# Programmer.net
KiCad netlist of a schematic drawn in Altium Designer
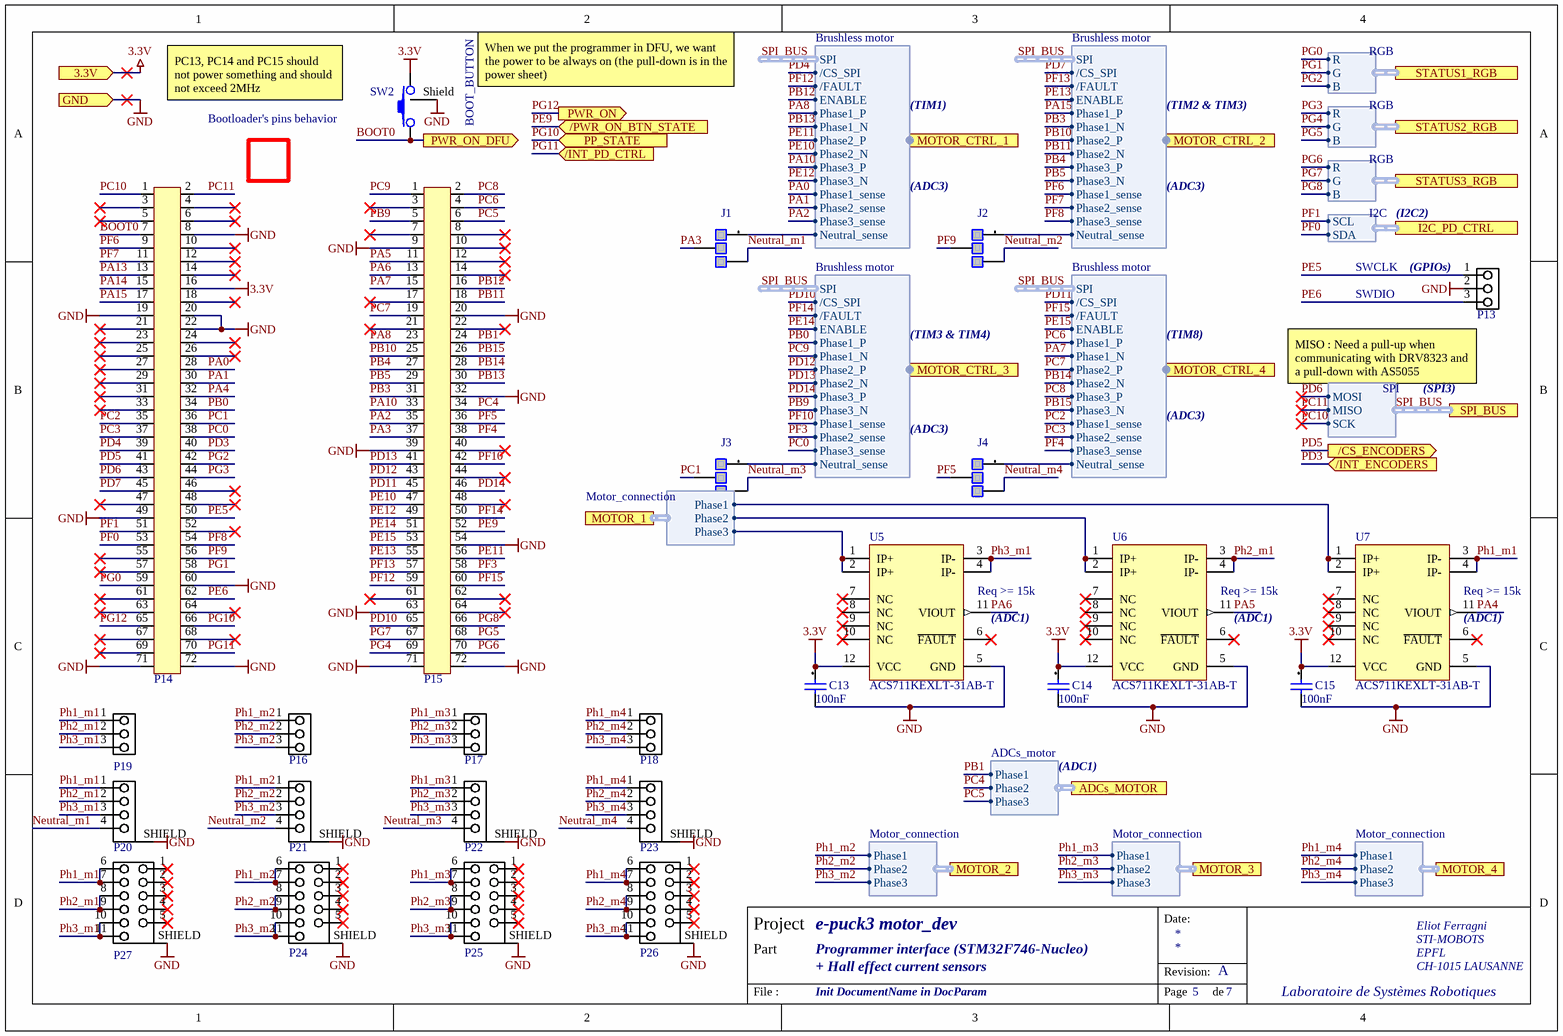
[diagram p0: Programmer.SchDoc]

(export (version "E")
  (design (tool "Eeschema 10.0.6"))
  (components
    (comp (ref "C13")
      (value "100nF")
      (footprint "CAPC1608X08L")
      (description "Capacitor TBD 0603")
      (libsource (lib "LSRO1Altium") (part "CAP-NP"))
    )
    (comp (ref "C14")
      (value "100nF")
      (footprint "CAPC1608X08L")
      (description "Capacitor TBD 0603")
      (libsource (lib "LSRO1Altium") (part "CAP-NP"))
    )
    (comp (ref "C15")
      (value "100nF")
      (footprint "CAPC1608X08L")
      (description "Capacitor TBD 0603")
      (libsource (lib "LSRO1Altium") (part "CAP-NP"))
    )
    (comp (ref "J1")
      (value "CC_SolderJP3_Micro")
      (footprint "CC_SolderJP3_U")
      (description "Micro Solder Jumper 3 leads")
      (libsource (lib "LSRO1Altium") (part "SolderJP3"))
    )
    (comp (ref "J2")
      (value "CC_SolderJP3_Micro")
      (footprint "CC_SolderJP3_U")
      (description "Micro Solder Jumper 3 leads")
      (libsource (lib "LSRO1Altium") (part "SolderJP3"))
    )
    (comp (ref "J3")
      (value "CC_SolderJP3_Micro")
      (footprint "CC_SolderJP3_U")
      (description "Micro Solder Jumper 3 leads")
      (libsource (lib "LSRO1Altium") (part "SolderJP3"))
    )
    (comp (ref "J4")
      (value "CC_SolderJP3_Micro")
      (footprint "CC_SolderJP3_U")
      (description "Micro Solder Jumper 3 leads")
      (libsource (lib "LSRO1Altium") (part "SolderJP3"))
    )
    (comp (ref "P13")
      (value "Header 3")
      (footprint "HEADER1X3-2.54")
      (description "Header, 3-Pin")
      (fields (field (name "MANUFACTURER") "Generic Components") (field (name "PUBLISHER") "Altium Limited"))
      (libsource (lib "Schlib") (part "Header 3"))
    )
    (comp (ref "P14")
      (value "Header 2x36")
      (footprint "HEADER2x36-2.54")
      (libsource (lib "Schlib") (part "Header 2x36"))
    )
    (comp (ref "P15")
      (value "Header 2x36")
      (footprint "HEADER2x36-2.54")
      (libsource (lib "Schlib") (part "Header 2x36"))
    )
    (comp (ref "P16")
      (value "3 power pads")
      (footprint "PowerPads 3 pins")
      (description "3-Pin")
      (fields (field (name "MANUFACTURER") "Generic Components") (field (name "PUBLISHER") "Altium Limited"))
      (libsource (lib "Schlib") (part "3 power pads"))
    )
    (comp (ref "P17")
      (value "3 power pads")
      (footprint "PowerPads 3 pins")
      (description "3-Pin")
      (fields (field (name "MANUFACTURER") "Generic Components") (field (name "PUBLISHER") "Altium Limited"))
      (libsource (lib "Schlib") (part "3 power pads"))
    )
    (comp (ref "P18")
      (value "3 power pads")
      (footprint "PowerPads 3 pins")
      (description "3-Pin")
      (fields (field (name "MANUFACTURER") "Generic Components") (field (name "PUBLISHER") "Altium Limited"))
      (libsource (lib "Schlib") (part "3 power pads"))
    )
    (comp (ref "P19")
      (value "3 power pads")
      (footprint "PowerPads 3 pins")
      (description "3-Pin")
      (fields (field (name "MANUFACTURER") "Generic Components") (field (name "PUBLISHER") "Altium Limited"))
      (libsource (lib "Schlib") (part "3 power pads"))
    )
    (comp (ref "P20")
      (value "MOLEX-52207-0433")
      (footprint "Molex 52207-0433")
      (libsource (lib "Schlib") (part "MOLEX-52207-0433"))
    )
    (comp (ref "P21")
      (value "MOLEX-52207-0433")
      (footprint "Molex 52207-0433")
      (libsource (lib "Schlib") (part "MOLEX-52207-0433"))
    )
    (comp (ref "P22")
      (value "MOLEX-52207-0433")
      (footprint "Molex 52207-0433")
      (libsource (lib "Schlib") (part "MOLEX-52207-0433"))
    )
    (comp (ref "P23")
      (value "MOLEX-52207-0433")
      (footprint "Molex 52207-0433")
      (libsource (lib "Schlib") (part "MOLEX-52207-0433"))
    )
    (comp (ref "P24")
      (value "MOLEX-52207-1133")
      (footprint "Molex 52207-1133")
      (libsource (lib "Schlib") (part "MOLEX-52207-1133"))
    )
    (comp (ref "P25")
      (value "MOLEX-52207-1133")
      (footprint "Molex 52207-1133")
      (libsource (lib "Schlib") (part "MOLEX-52207-1133"))
    )
    (comp (ref "P26")
      (value "MOLEX-52207-1133")
      (footprint "Molex 52207-1133")
      (libsource (lib "Schlib") (part "MOLEX-52207-1133"))
    )
    (comp (ref "P27")
      (value "MOLEX-52207-1133")
      (footprint "Molex 52207-1133")
      (libsource (lib "Schlib") (part "MOLEX-52207-1133"))
    )
    (comp (ref "SW2")
      (value "button")
      (footprint "C&K_KMR2")
      (description "KMR221GLFS")
      (fields (field (name "MANUFACTURER") "Tyco"))
      (libsource (lib "Schlib") (part "C&K KMR2"))
    )
    (comp (ref "U5")
      (value "ACS711KEXLT-31AB-T")
      (footprint "12-PowerWFQFN")
      (libsource (lib "Schlib") (part "ACS711KEXLT-31AB-T"))
    )
    (comp (ref "U6")
      (value "ACS711KEXLT-31AB-T")
      (footprint "12-PowerWFQFN")
      (libsource (lib "Schlib") (part "ACS711KEXLT-31AB-T"))
    )
    (comp (ref "U7")
      (value "ACS711KEXLT-31AB-T")
      (footprint "12-PowerWFQFN")
      (libsource (lib "Schlib") (part "ACS711KEXLT-31AB-T"))
    )
  )
  (nets
    (net (code "16") (name "/BOOT0") (class "Default")
      (node (ref "P14") (pin "7") (pinfunction "7_7") (pintype "passive"))
      (node (ref "SW2") (pin "1") (pintype "passive"))
    )
    (net (code "21") (name "/Neutral_m1") (class "Default")
      (node (ref "J1") (pin "3") (pintype "passive"))
      (node (ref "P20") (pin "4") (pinfunction "4_4") (pintype "passive"))
    )
    (net (code "22") (name "/Neutral_m2") (class "Default")
      (node (ref "J2") (pin "3") (pintype "passive"))
      (node (ref "P21") (pin "4") (pinfunction "4_4") (pintype "passive"))
    )
    (net (code "23") (name "/Neutral_m3") (class "Default")
      (node (ref "J3") (pin "3") (pintype "passive"))
      (node (ref "P22") (pin "4") (pinfunction "4_4") (pintype "passive"))
    )
    (net (code "24") (name "/Neutral_m4") (class "Default")
      (node (ref "J4") (pin "3") (pintype "passive"))
      (node (ref "P23") (pin "4") (pinfunction "4_4") (pintype "passive"))
    )
    (net (code "25") (name "/PA0") (class "Default")
      (node (ref "P14") (pin "28") (pinfunction "28_28") (pintype "passive"))
    )
    (net (code "26") (name "/PA1") (class "Default")
      (node (ref "P14") (pin "30") (pinfunction "30_30") (pintype "passive"))
    )
    (net (code "27") (name "/PA2") (class "Default")
      (node (ref "P15") (pin "35") (pinfunction "35_35") (pintype "passive"))
    )
    (net (code "28") (name "/PA3") (class "Default")
      (node (ref "J1") (pin "2") (pintype "passive"))
      (node (ref "P15") (pin "37") (pinfunction "37_37") (pintype "passive"))
    )
    (net (code "29") (name "/PA4") (class "Default")
      (node (ref "P14") (pin "32") (pinfunction "32_32") (pintype "passive"))
      (node (ref "U7") (pin "11") (pinfunction "VIOUT_11") (pintype "output"))
    )
    (net (code "30") (name "/PA5") (class "Default")
      (node (ref "P15") (pin "11") (pinfunction "11_11") (pintype "passive"))
      (node (ref "U6") (pin "11") (pinfunction "VIOUT_11") (pintype "output"))
    )
    (net (code "31") (name "/PA6") (class "Default")
      (node (ref "P15") (pin "13") (pinfunction "13_13") (pintype "passive"))
      (node (ref "U5") (pin "11") (pinfunction "VIOUT_11") (pintype "output"))
    )
    (net (code "32") (name "/PA7") (class "Default")
      (node (ref "P15") (pin "15") (pinfunction "15_15") (pintype "passive"))
    )
    (net (code "33") (name "/PA8") (class "Default")
      (node (ref "P15") (pin "23") (pinfunction "23_23") (pintype "passive"))
    )
    (net (code "34") (name "/PA10") (class "Default")
      (node (ref "P15") (pin "33") (pinfunction "33_33") (pintype "passive"))
    )
    (net (code "35") (name "/PA13") (class "Default")
      (node (ref "P14") (pin "13") (pinfunction "13_13") (pintype "passive"))
    )
    (net (code "36") (name "/PA14") (class "Default")
      (node (ref "P14") (pin "15") (pinfunction "15_15") (pintype "passive"))
    )
    (net (code "37") (name "/PA15") (class "Default")
      (node (ref "P14") (pin "17") (pinfunction "17_17") (pintype "passive"))
    )
    (net (code "38") (name "/PB0") (class "Default")
      (node (ref "P14") (pin "34") (pinfunction "34_34") (pintype "passive"))
    )
    (net (code "39") (name "/PB1") (class "Default")
      (node (ref "P15") (pin "24") (pinfunction "24_24") (pintype "passive"))
    )
    (net (code "40") (name "/PB3") (class "Default")
      (node (ref "P15") (pin "31") (pinfunction "31_31") (pintype "passive"))
    )
    (net (code "41") (name "/PB4") (class "Default")
      (node (ref "P15") (pin "27") (pinfunction "27_27") (pintype "passive"))
    )
    (net (code "42") (name "/PB5") (class "Default")
      (node (ref "P15") (pin "29") (pinfunction "29_29") (pintype "passive"))
    )
    (net (code "43") (name "/PB9") (class "Default")
      (node (ref "P15") (pin "5") (pinfunction "5_5") (pintype "passive"))
    )
    (net (code "44") (name "/PB10") (class "Default")
      (node (ref "P15") (pin "25") (pinfunction "25_25") (pintype "passive"))
    )
    (net (code "45") (name "/PB11") (class "Default")
      (node (ref "P15") (pin "18") (pinfunction "18_18") (pintype "passive"))
    )
    (net (code "46") (name "/PB12") (class "Default")
      (node (ref "P15") (pin "16") (pinfunction "16_16") (pintype "passive"))
    )
    (net (code "47") (name "/PB13") (class "Default")
      (node (ref "P15") (pin "30") (pinfunction "30_30") (pintype "passive"))
    )
    (net (code "48") (name "/PB14") (class "Default")
      (node (ref "P15") (pin "28") (pinfunction "28_28") (pintype "passive"))
    )
    (net (code "49") (name "/PB15") (class "Default")
      (node (ref "P15") (pin "26") (pinfunction "26_26") (pintype "passive"))
    )
    (net (code "50") (name "/PC0") (class "Default")
      (node (ref "P14") (pin "38") (pinfunction "38_38") (pintype "passive"))
    )
    (net (code "51") (name "/PC1") (class "Default")
      (node (ref "J3") (pin "2") (pintype "passive"))
      (node (ref "P14") (pin "36") (pinfunction "36_36") (pintype "passive"))
    )
    (net (code "52") (name "/PC2") (class "Default")
      (node (ref "P14") (pin "35") (pinfunction "35_35") (pintype "passive"))
    )
    (net (code "53") (name "/PC3") (class "Default")
      (node (ref "P14") (pin "37") (pinfunction "37_37") (pintype "passive"))
    )
    (net (code "54") (name "/PC4") (class "Default")
      (node (ref "P15") (pin "34") (pinfunction "34_34") (pintype "passive"))
    )
    (net (code "55") (name "/PC5") (class "Default")
      (node (ref "P15") (pin "6") (pinfunction "6_6") (pintype "passive"))
    )
    (net (code "56") (name "/PC6") (class "Default")
      (node (ref "P15") (pin "4") (pinfunction "4_4") (pintype "passive"))
    )
    (net (code "57") (name "/PC7") (class "Default")
      (node (ref "P15") (pin "19") (pinfunction "19_19") (pintype "passive"))
    )
    (net (code "58") (name "/PC8") (class "Default")
      (node (ref "P15") (pin "2") (pinfunction "2_2") (pintype "passive"))
    )
    (net (code "59") (name "/PC9") (class "Default")
      (node (ref "P15") (pin "1") (pinfunction "1_1") (pintype "passive"))
    )
    (net (code "60") (name "/PC10") (class "Default")
      (node (ref "P14") (pin "1") (pinfunction "1_1") (pintype "passive+no_connect"))
    )
    (net (code "61") (name "/PC11") (class "Default")
      (node (ref "P14") (pin "2") (pinfunction "2_2") (pintype "passive+no_connect"))
    )
    (net (code "62") (name "/PD3") (class "Default")
      (node (ref "P14") (pin "40") (pinfunction "40_40") (pintype "passive"))
    )
    (net (code "63") (name "/PD4") (class "Default")
      (node (ref "P14") (pin "39") (pinfunction "39_39") (pintype "passive"))
    )
    (net (code "64") (name "/PD5") (class "Default")
      (node (ref "P14") (pin "41") (pinfunction "41_41") (pintype "passive"))
    )
    (net (code "65") (name "/PD6") (class "Default")
      (node (ref "P14") (pin "43") (pinfunction "43_43") (pintype "passive+no_connect"))
    )
    (net (code "66") (name "/PD7") (class "Default")
      (node (ref "P14") (pin "45") (pinfunction "45_45") (pintype "passive"))
    )
    (net (code "67") (name "/PD10") (class "Default")
      (node (ref "P15") (pin "65") (pinfunction "57_65") (pintype "passive"))
    )
    (net (code "68") (name "/PD11") (class "Default")
      (node (ref "P15") (pin "45") (pinfunction "45_45") (pintype "passive"))
    )
    (net (code "69") (name "/PD12") (class "Default")
      (node (ref "P15") (pin "43") (pinfunction "43_43") (pintype "passive"))
    )
    (net (code "70") (name "/PD13") (class "Default")
      (node (ref "P15") (pin "41") (pinfunction "41_41") (pintype "passive"))
    )
    (net (code "71") (name "/PD14") (class "Default")
      (node (ref "P15") (pin "46") (pinfunction "46_46") (pintype "passive"))
    )
    (net (code "72") (name "/PE5") (class "Default")
      (node (ref "P13") (pin "1") (pinfunction "1_1") (pintype "passive"))
      (node (ref "P14") (pin "50") (pinfunction "50_50") (pintype "passive"))
    )
    (net (code "73") (name "/PE6") (class "Default")
      (node (ref "P13") (pin "3") (pinfunction "3_3") (pintype "passive"))
      (node (ref "P14") (pin "62") (pinfunction "56_62") (pintype "passive"))
    )
    (net (code "74") (name "/PE9") (class "Default")
      (node (ref "P15") (pin "52") (pinfunction "51_52") (pintype "passive"))
    )
    (net (code "75") (name "/PE10") (class "Default")
      (node (ref "P15") (pin "47") (pinfunction "47_47") (pintype "passive"))
    )
    (net (code "76") (name "/PE11") (class "Default")
      (node (ref "P15") (pin "56") (pinfunction "53_56") (pintype "passive"))
    )
    (net (code "77") (name "/PE12") (class "Default")
      (node (ref "P15") (pin "49") (pinfunction "49_49") (pintype "passive"))
    )
    (net (code "78") (name "/PE13") (class "Default")
      (node (ref "P15") (pin "55") (pinfunction "52_55") (pintype "passive"))
    )
    (net (code "79") (name "/PE14") (class "Default")
      (node (ref "P15") (pin "51") (pinfunction "50_51") (pintype "passive"))
    )
    (net (code "80") (name "/PE15") (class "Default")
      (node (ref "P15") (pin "53") (pinfunction "51_53") (pintype "passive"))
    )
    (net (code "81") (name "/PF0") (class "Default")
      (node (ref "P14") (pin "53") (pinfunction "51_53") (pintype "passive"))
    )
    (net (code "82") (name "/PF1") (class "Default")
      (node (ref "P14") (pin "51") (pinfunction "50_51") (pintype "passive"))
    )
    (net (code "83") (name "/PF3") (class "Default")
      (node (ref "P15") (pin "58") (pinfunction "54_58") (pintype "passive"))
    )
    (net (code "84") (name "/PF4") (class "Default")
      (node (ref "P15") (pin "38") (pinfunction "38_38") (pintype "passive"))
    )
    (net (code "85") (name "/PF5") (class "Default")
      (node (ref "J4") (pin "2") (pintype "passive"))
      (node (ref "P15") (pin "36") (pinfunction "36_36") (pintype "passive"))
    )
    (net (code "86") (name "/PF6") (class "Default")
      (node (ref "P14") (pin "9") (pinfunction "9_9") (pintype "passive"))
    )
    (net (code "87") (name "/PF7") (class "Default")
      (node (ref "P14") (pin "11") (pinfunction "11_11") (pintype "passive"))
    )
    (net (code "88") (name "/PF8") (class "Default")
      (node (ref "P14") (pin "54") (pinfunction "52_54") (pintype "passive"))
    )
    (net (code "89") (name "/PF9") (class "Default")
      (node (ref "J2") (pin "2") (pintype "passive"))
      (node (ref "P14") (pin "56") (pinfunction "53_56") (pintype "passive"))
    )
    (net (code "90") (name "/PF10") (class "Default")
      (node (ref "P15") (pin "42") (pinfunction "42_42") (pintype "passive"))
    )
    (net (code "91") (name "/PF12") (class "Default")
      (node (ref "P15") (pin "59") (pinfunction "54_59") (pintype "passive"))
    )
    (net (code "92") (name "/PF13") (class "Default")
      (node (ref "P15") (pin "57") (pinfunction "53_57") (pintype "passive"))
    )
    (net (code "93") (name "/PF14") (class "Default")
      (node (ref "P15") (pin "50") (pinfunction "50_50") (pintype "passive"))
    )
    (net (code "94") (name "/PF15") (class "Default")
      (node (ref "P15") (pin "60") (pinfunction "55_60") (pintype "passive"))
    )
    (net (code "95") (name "/PG0") (class "Default")
      (node (ref "P14") (pin "59") (pinfunction "54_59") (pintype "passive"))
    )
    (net (code "96") (name "/PG1") (class "Default")
      (node (ref "P14") (pin "58") (pinfunction "54_58") (pintype "passive"))
    )
    (net (code "97") (name "/PG2") (class "Default")
      (node (ref "P14") (pin "42") (pinfunction "42_42") (pintype "passive"))
    )
    (net (code "98") (name "/PG3") (class "Default")
      (node (ref "P14") (pin "44") (pinfunction "44_44") (pintype "passive"))
    )
    (net (code "99") (name "/PG4") (class "Default")
      (node (ref "P15") (pin "69") (pinfunction "59_69") (pintype "passive"))
    )
    (net (code "100") (name "/PG5") (class "Default")
      (node (ref "P15") (pin "68") (pinfunction "59_68") (pintype "passive"))
    )
    (net (code "101") (name "/PG6") (class "Default")
      (node (ref "P15") (pin "70") (pinfunction "60_70") (pintype "passive"))
    )
    (net (code "102") (name "/PG7") (class "Default")
      (node (ref "P15") (pin "67") (pinfunction "58_67") (pintype "passive"))
    )
    (net (code "103") (name "/PG8") (class "Default")
      (node (ref "P15") (pin "66") (pinfunction "58_66") (pintype "passive"))
    )
    (net (code "104") (name "/PG10") (class "Default")
      (node (ref "P14") (pin "66") (pinfunction "58_66") (pintype "passive"))
    )
    (net (code "105") (name "/PG11") (class "Default")
      (node (ref "P14") (pin "70") (pinfunction "60_70") (pintype "passive"))
    )
    (net (code "106") (name "/PG12") (class "Default")
      (node (ref "P14") (pin "65") (pinfunction "57_65") (pintype "passive"))
    )
    (net (code "107") (name "/Ph1_m1") (class "Default")
      (node (ref "P19") (pin "1") (pinfunction "1_1") (pintype "passive"))
      (node (ref "P20") (pin "1") (pinfunction "1_1") (pintype "passive"))
      (node (ref "P27") (pin "6") (pinfunction "6_6") (pintype "passive"))
      (node (ref "P27") (pin "7") (pinfunction "7_7") (pintype "passive"))
      (node (ref "U7") (pin "3") (pinfunction "IP-_3") (pintype "power_in"))
      (node (ref "U7") (pin "4") (pinfunction "IP-_4") (pintype "power_in"))
    )
    (net (code "108") (name "/Ph1_m2") (class "Default")
      (node (ref "P16") (pin "1") (pinfunction "1_1") (pintype "passive"))
      (node (ref "P21") (pin "1") (pinfunction "1_1") (pintype "passive"))
      (node (ref "P24") (pin "6") (pinfunction "6_6") (pintype "passive"))
      (node (ref "P24") (pin "7") (pinfunction "7_7") (pintype "passive"))
    )
    (net (code "109") (name "/Ph1_m3") (class "Default")
      (node (ref "P17") (pin "1") (pinfunction "1_1") (pintype "passive"))
      (node (ref "P22") (pin "1") (pinfunction "1_1") (pintype "passive"))
      (node (ref "P25") (pin "6") (pinfunction "6_6") (pintype "passive"))
      (node (ref "P25") (pin "7") (pinfunction "7_7") (pintype "passive"))
    )
    (net (code "110") (name "/Ph1_m4") (class "Default")
      (node (ref "P18") (pin "1") (pinfunction "1_1") (pintype "passive"))
      (node (ref "P23") (pin "1") (pinfunction "1_1") (pintype "passive"))
      (node (ref "P26") (pin "6") (pinfunction "6_6") (pintype "passive"))
      (node (ref "P26") (pin "7") (pinfunction "7_7") (pintype "passive"))
    )
    (net (code "111") (name "/Ph2_m1") (class "Default")
      (node (ref "P19") (pin "2") (pinfunction "2_2") (pintype "passive"))
      (node (ref "P20") (pin "2") (pinfunction "2_2") (pintype "passive"))
      (node (ref "P27") (pin "8") (pinfunction "8_8") (pintype "passive"))
      (node (ref "P27") (pin "9") (pinfunction "9_9") (pintype "passive"))
      (node (ref "U6") (pin "3") (pinfunction "IP-_3") (pintype "power_in"))
      (node (ref "U6") (pin "4") (pinfunction "IP-_4") (pintype "power_in"))
    )
    (net (code "112") (name "/Ph2_m2") (class "Default")
      (node (ref "P16") (pin "2") (pinfunction "2_2") (pintype "passive"))
      (node (ref "P21") (pin "2") (pinfunction "2_2") (pintype "passive"))
      (node (ref "P24") (pin "8") (pinfunction "8_8") (pintype "passive"))
      (node (ref "P24") (pin "9") (pinfunction "9_9") (pintype "passive"))
    )
    (net (code "113") (name "/Ph2_m3") (class "Default")
      (node (ref "P17") (pin "2") (pinfunction "2_2") (pintype "passive"))
      (node (ref "P22") (pin "2") (pinfunction "2_2") (pintype "passive"))
      (node (ref "P25") (pin "8") (pinfunction "8_8") (pintype "passive"))
      (node (ref "P25") (pin "9") (pinfunction "9_9") (pintype "passive"))
    )
    (net (code "114") (name "/Ph2_m4") (class "Default")
      (node (ref "P18") (pin "2") (pinfunction "2_2") (pintype "passive"))
      (node (ref "P23") (pin "2") (pinfunction "2_2") (pintype "passive"))
      (node (ref "P26") (pin "8") (pinfunction "8_8") (pintype "passive"))
      (node (ref "P26") (pin "9") (pinfunction "9_9") (pintype "passive"))
    )
    (net (code "115") (name "/Ph3_m1") (class "Default")
      (node (ref "P19") (pin "3") (pinfunction "3_3") (pintype "passive"))
      (node (ref "P20") (pin "3") (pinfunction "3_3") (pintype "passive"))
      (node (ref "P27") (pin "10") (pinfunction "10_10") (pintype "passive"))
      (node (ref "P27") (pin "11") (pinfunction "11_11") (pintype "passive"))
      (node (ref "U5") (pin "3") (pinfunction "IP-_3") (pintype "power_in"))
      (node (ref "U5") (pin "4") (pinfunction "IP-_4") (pintype "power_in"))
    )
    (net (code "116") (name "/Ph3_m2") (class "Default")
      (node (ref "P16") (pin "3") (pinfunction "3_3") (pintype "passive"))
      (node (ref "P21") (pin "3") (pinfunction "3_3") (pintype "passive"))
      (node (ref "P24") (pin "10") (pinfunction "10_10") (pintype "passive"))
      (node (ref "P24") (pin "11") (pinfunction "11_11") (pintype "passive"))
    )
    (net (code "117") (name "/Ph3_m3") (class "Default")
      (node (ref "P17") (pin "3") (pinfunction "3_3") (pintype "passive"))
      (node (ref "P22") (pin "3") (pinfunction "3_3") (pintype "passive"))
      (node (ref "P25") (pin "10") (pinfunction "10_10") (pintype "passive"))
      (node (ref "P25") (pin "11") (pinfunction "11_11") (pintype "passive"))
    )
    (net (code "118") (name "/Ph3_m4") (class "Default")
      (node (ref "P18") (pin "3") (pinfunction "3_3") (pintype "passive"))
      (node (ref "P23") (pin "3") (pinfunction "3_3") (pintype "passive"))
      (node (ref "P26") (pin "10") (pinfunction "10_10") (pintype "passive"))
      (node (ref "P26") (pin "11") (pinfunction "11_11") (pintype "passive"))
    )
    (net (code "125") (name "3.3V") (class "Default")
      (node (ref "C13") (pin "1") (pinfunction "1_1") (pintype "passive"))
      (node (ref "C14") (pin "1") (pinfunction "1_1") (pintype "passive"))
      (node (ref "C15") (pin "1") (pinfunction "1_1") (pintype "passive"))
      (node (ref "P14") (pin "16") (pinfunction "16_16") (pintype "passive"))
      (node (ref "SW2") (pin "2") (pintype "passive"))
      (node (ref "U5") (pin "12") (pinfunction "VCC_12") (pintype "power_in"))
      (node (ref "U6") (pin "12") (pinfunction "VCC_12") (pintype "power_in"))
      (node (ref "U7") (pin "12") (pinfunction "VCC_12") (pintype "power_in"))
    )
    (net (code "126") (name "GND") (class "Default")
      (node (ref "C13") (pin "2") (pinfunction "2_2") (pintype "passive"))
      (node (ref "C14") (pin "2") (pinfunction "2_2") (pintype "passive"))
      (node (ref "C15") (pin "2") (pinfunction "2_2") (pintype "passive"))
      (node (ref "P13") (pin "2") (pinfunction "2_2") (pintype "passive"))
      (node (ref "P14") (pin "19") (pinfunction "19_19") (pintype "passive"))
      (node (ref "P14") (pin "20") (pinfunction "20_20") (pintype "passive"))
      (node (ref "P14") (pin "22") (pinfunction "22_22") (pintype "passive"))
      (node (ref "P14") (pin "49") (pinfunction "49_49") (pintype "passive"))
      (node (ref "P14") (pin "60") (pinfunction "55_60") (pintype "passive"))
      (node (ref "P14") (pin "71") (pinfunction "60_71") (pintype "passive"))
      (node (ref "P14") (pin "72") (pinfunction "61_72") (pintype "passive"))
      (node (ref "P14") (pin "8") (pinfunction "8_8") (pintype "passive"))
      (node (ref "P15") (pin "20") (pinfunction "20_20") (pintype "passive"))
      (node (ref "P15") (pin "32") (pinfunction "32_32") (pintype "passive"))
      (node (ref "P15") (pin "39") (pinfunction "39_39") (pintype "passive"))
      (node (ref "P15") (pin "54") (pinfunction "52_54") (pintype "passive"))
      (node (ref "P15") (pin "63") (pinfunction "56_63") (pintype "passive"))
      (node (ref "P15") (pin "71") (pinfunction "60_71") (pintype "passive"))
      (node (ref "P15") (pin "72") (pinfunction "61_72") (pintype "passive"))
      (node (ref "P15") (pin "9") (pinfunction "9_9") (pintype "passive"))
      (node (ref "P20") (pin "SHIELD") (pinfunction "SHIELD_SHIELD") (pintype "passive"))
      (node (ref "P21") (pin "SHIELD") (pinfunction "SHIELD_SHIELD") (pintype "passive"))
      (node (ref "P22") (pin "SHIELD") (pinfunction "SHIELD_SHIELD") (pintype "passive"))
      (node (ref "P23") (pin "SHIELD") (pinfunction "SHIELD_SHIELD") (pintype "passive"))
      (node (ref "P24") (pin "SHIELD") (pinfunction "SHIELD_SHIELD") (pintype "passive"))
      (node (ref "P25") (pin "SHIELD") (pinfunction "SHIELD_SHIELD") (pintype "passive"))
      (node (ref "P26") (pin "SHIELD") (pinfunction "SHIELD_SHIELD") (pintype "passive"))
      (node (ref "P27") (pin "SHIELD") (pinfunction "SHIELD_SHIELD") (pintype "passive"))
      (node (ref "SW2") (pin "Shield") (pinfunction "Shield_Shield") (pintype "passive"))
      (node (ref "U5") (pin "5") (pinfunction "GND_5") (pintype "power_in"))
      (node (ref "U6") (pin "5") (pinfunction "GND_5") (pintype "power_in"))
      (node (ref "U7") (pin "5") (pinfunction "GND_5") (pintype "power_in"))
    )
    (net (code "127") (name "Net-(U5-IP+-Pad1)") (class "Default")
      (node (ref "U5") (pin "1") (pinfunction "IP+_1") (pintype "power_in"))
      (node (ref "U5") (pin "2") (pinfunction "IP+_2") (pintype "power_in"))
    )
    (net (code "128") (name "Net-(U6-IP+-Pad1)") (class "Default")
      (node (ref "U6") (pin "1") (pinfunction "IP+_1") (pintype "power_in"))
      (node (ref "U6") (pin "2") (pinfunction "IP+_2") (pintype "power_in"))
    )
    (net (code "129") (name "Net-(U7-IP+-Pad1)") (class "Default")
      (node (ref "U7") (pin "1") (pinfunction "IP+_1") (pintype "power_in"))
      (node (ref "U7") (pin "2") (pinfunction "IP+_2") (pintype "power_in"))
    )
    (net (code "130") (name "unconnected-(J1-Pad1)") (class "Default")
      (node (ref "J1") (pin "1") (pintype "passive"))
    )
    (net (code "131") (name "unconnected-(J2-Pad1)") (class "Default")
      (node (ref "J2") (pin "1") (pintype "passive"))
    )
    (net (code "132") (name "unconnected-(J3-Pad1)") (class "Default")
      (node (ref "J3") (pin "1") (pintype "passive"))
    )
    (net (code "133") (name "unconnected-(J4-Pad1)") (class "Default")
      (node (ref "J4") (pin "1") (pintype "passive"))
    )
    (net (code "134") (name "unconnected-(P14-51-Pad52)") (class "Default")
      (node (ref "P14") (pin "52") (pinfunction "51_52") (pintype "passive+no_connect"))
    )
    (net (code "135") (name "unconnected-(P14-52-Pad55)") (class "Default")
      (node (ref "P14") (pin "55") (pinfunction "52_55") (pintype "passive+no_connect"))
    )
    (net (code "136") (name "unconnected-(P14-53-Pad57)") (class "Default")
      (node (ref "P14") (pin "57") (pinfunction "53_57") (pintype "passive+no_connect"))
    )
    (net (code "137") (name "unconnected-(P14-55-Pad61)") (class "Default")
      (node (ref "P14") (pin "61") (pinfunction "55_61") (pintype "passive+no_connect"))
    )
    (net (code "138") (name "unconnected-(P14-56-Pad63)") (class "Default")
      (node (ref "P14") (pin "63") (pinfunction "56_63") (pintype "passive+no_connect"))
    )
    (net (code "139") (name "unconnected-(P14-57-Pad64)") (class "Default")
      (node (ref "P14") (pin "64") (pinfunction "57_64") (pintype "passive+no_connect"))
    )
    (net (code "140") (name "unconnected-(P14-58-Pad67)") (class "Default")
      (node (ref "P14") (pin "67") (pinfunction "58_67") (pintype "passive+no_connect"))
    )
    (net (code "141") (name "unconnected-(P14-59-Pad68)") (class "Default")
      (node (ref "P14") (pin "68") (pinfunction "59_68") (pintype "passive+no_connect"))
    )
    (net (code "142") (name "unconnected-(P14-59-Pad69)") (class "Default")
      (node (ref "P14") (pin "69") (pinfunction "59_69") (pintype "passive+no_connect"))
    )
    (net (code "143") (name "unconnected-(P14-Pad3)") (class "Default")
      (node (ref "P14") (pin "3") (pinfunction "3_3") (pintype "passive+no_connect"))
    )
    (net (code "144") (name "unconnected-(P14-Pad4)") (class "Default")
      (node (ref "P14") (pin "4") (pinfunction "4_4") (pintype "passive+no_connect"))
    )
    (net (code "145") (name "unconnected-(P14-Pad5)") (class "Default")
      (node (ref "P14") (pin "5") (pinfunction "5_5") (pintype "passive+no_connect"))
    )
    (net (code "146") (name "unconnected-(P14-Pad6)") (class "Default")
      (node (ref "P14") (pin "6") (pinfunction "6_6") (pintype "passive+no_connect"))
    )
    (net (code "147") (name "unconnected-(P14-Pad10)") (class "Default")
      (node (ref "P14") (pin "10") (pinfunction "10_10") (pintype "passive+no_connect"))
    )
    (net (code "148") (name "unconnected-(P14-Pad12)") (class "Default")
      (node (ref "P14") (pin "12") (pinfunction "12_12") (pintype "passive+no_connect"))
    )
    (net (code "149") (name "unconnected-(P14-Pad14)") (class "Default")
      (node (ref "P14") (pin "14") (pinfunction "14_14") (pintype "passive+no_connect"))
    )
    (net (code "150") (name "unconnected-(P14-Pad18)") (class "Default")
      (node (ref "P14") (pin "18") (pinfunction "18_18") (pintype "passive+no_connect"))
    )
    (net (code "151") (name "unconnected-(P14-Pad21)") (class "Default")
      (node (ref "P14") (pin "21") (pinfunction "21_21") (pintype "passive+no_connect"))
    )
    (net (code "152") (name "unconnected-(P14-Pad23)") (class "Default")
      (node (ref "P14") (pin "23") (pinfunction "23_23") (pintype "passive+no_connect"))
    )
    (net (code "153") (name "unconnected-(P14-Pad24)") (class "Default")
      (node (ref "P14") (pin "24") (pinfunction "24_24") (pintype "passive+no_connect"))
    )
    (net (code "154") (name "unconnected-(P14-Pad25)") (class "Default")
      (node (ref "P14") (pin "25") (pinfunction "25_25") (pintype "passive+no_connect"))
    )
    (net (code "155") (name "unconnected-(P14-Pad26)") (class "Default")
      (node (ref "P14") (pin "26") (pinfunction "26_26") (pintype "passive+no_connect"))
    )
    (net (code "156") (name "unconnected-(P14-Pad27)") (class "Default")
      (node (ref "P14") (pin "27") (pinfunction "27_27") (pintype "passive+no_connect"))
    )
    (net (code "157") (name "unconnected-(P14-Pad29)") (class "Default")
      (node (ref "P14") (pin "29") (pinfunction "29_29") (pintype "passive+no_connect"))
    )
    (net (code "158") (name "unconnected-(P14-Pad31)") (class "Default")
      (node (ref "P14") (pin "31") (pinfunction "31_31") (pintype "passive+no_connect"))
    )
    (net (code "159") (name "unconnected-(P14-Pad33)") (class "Default")
      (node (ref "P14") (pin "33") (pinfunction "33_33") (pintype "passive+no_connect"))
    )
    (net (code "160") (name "unconnected-(P14-Pad46)") (class "Default")
      (node (ref "P14") (pin "46") (pinfunction "46_46") (pintype "passive+no_connect"))
    )
    (net (code "161") (name "unconnected-(P14-Pad47)") (class "Default")
      (node (ref "P14") (pin "47") (pinfunction "47_47") (pintype "passive+no_connect"))
    )
    (net (code "162") (name "unconnected-(P14-Pad48)") (class "Default")
      (node (ref "P14") (pin "48") (pinfunction "48_48") (pintype "passive+no_connect"))
    )
    (net (code "163") (name "unconnected-(P15-55-Pad61)") (class "Default")
      (node (ref "P15") (pin "61") (pinfunction "55_61") (pintype "passive+no_connect"))
    )
    (net (code "164") (name "unconnected-(P15-56-Pad62)") (class "Default")
      (node (ref "P15") (pin "62") (pinfunction "56_62") (pintype "passive+no_connect"))
    )
    (net (code "165") (name "unconnected-(P15-57-Pad64)") (class "Default")
      (node (ref "P15") (pin "64") (pinfunction "57_64") (pintype "passive+no_connect"))
    )
    (net (code "166") (name "unconnected-(P15-Pad3)") (class "Default")
      (node (ref "P15") (pin "3") (pinfunction "3_3") (pintype "passive+no_connect"))
    )
    (net (code "167") (name "unconnected-(P15-Pad7)") (class "Default")
      (node (ref "P15") (pin "7") (pinfunction "7_7") (pintype "passive+no_connect"))
    )
    (net (code "168") (name "unconnected-(P15-Pad8)") (class "Default")
      (node (ref "P15") (pin "8") (pinfunction "8_8") (pintype "passive+no_connect"))
    )
    (net (code "169") (name "unconnected-(P15-Pad10)") (class "Default")
      (node (ref "P15") (pin "10") (pinfunction "10_10") (pintype "passive+no_connect"))
    )
    (net (code "170") (name "unconnected-(P15-Pad12)") (class "Default")
      (node (ref "P15") (pin "12") (pinfunction "12_12") (pintype "passive+no_connect"))
    )
    (net (code "171") (name "unconnected-(P15-Pad14)") (class "Default")
      (node (ref "P15") (pin "14") (pinfunction "14_14") (pintype "passive+no_connect"))
    )
    (net (code "172") (name "unconnected-(P15-Pad17)") (class "Default")
      (node (ref "P15") (pin "17") (pinfunction "17_17") (pintype "passive+no_connect"))
    )
    (net (code "173") (name "unconnected-(P15-Pad21)") (class "Default")
      (node (ref "P15") (pin "21") (pinfunction "21_21") (pintype "passive+no_connect"))
    )
    (net (code "174") (name "unconnected-(P15-Pad22)") (class "Default")
      (node (ref "P15") (pin "22") (pinfunction "22_22") (pintype "passive+no_connect"))
    )
    (net (code "175") (name "unconnected-(P15-Pad40)") (class "Default")
      (node (ref "P15") (pin "40") (pinfunction "40_40") (pintype "passive+no_connect"))
    )
    (net (code "176") (name "unconnected-(P15-Pad44)") (class "Default")
      (node (ref "P15") (pin "44") (pinfunction "44_44") (pintype "passive+no_connect"))
    )
    (net (code "177") (name "unconnected-(P15-Pad48)") (class "Default")
      (node (ref "P15") (pin "48") (pinfunction "48_48") (pintype "passive+no_connect"))
    )
    (net (code "178") (name "unconnected-(P24-Pad1)") (class "Default")
      (node (ref "P24") (pin "1") (pinfunction "1_1") (pintype "passive+no_connect"))
    )
    (net (code "179") (name "unconnected-(P24-Pad2)") (class "Default")
      (node (ref "P24") (pin "2") (pinfunction "2_2") (pintype "passive+no_connect"))
    )
    (net (code "180") (name "unconnected-(P24-Pad3)") (class "Default")
      (node (ref "P24") (pin "3") (pinfunction "3_3") (pintype "passive+no_connect"))
    )
    (net (code "181") (name "unconnected-(P24-Pad4)") (class "Default")
      (node (ref "P24") (pin "4") (pinfunction "4_4") (pintype "passive+no_connect"))
    )
    (net (code "182") (name "unconnected-(P24-Pad5)") (class "Default")
      (node (ref "P24") (pin "5") (pinfunction "5_5") (pintype "passive+no_connect"))
    )
    (net (code "183") (name "unconnected-(P25-Pad1)") (class "Default")
      (node (ref "P25") (pin "1") (pinfunction "1_1") (pintype "passive+no_connect"))
    )
    (net (code "184") (name "unconnected-(P25-Pad2)") (class "Default")
      (node (ref "P25") (pin "2") (pinfunction "2_2") (pintype "passive+no_connect"))
    )
    (net (code "185") (name "unconnected-(P25-Pad3)") (class "Default")
      (node (ref "P25") (pin "3") (pinfunction "3_3") (pintype "passive+no_connect"))
    )
    (net (code "186") (name "unconnected-(P25-Pad4)") (class "Default")
      (node (ref "P25") (pin "4") (pinfunction "4_4") (pintype "passive+no_connect"))
    )
    (net (code "187") (name "unconnected-(P25-Pad5)") (class "Default")
      (node (ref "P25") (pin "5") (pinfunction "5_5") (pintype "passive+no_connect"))
    )
    (net (code "188") (name "unconnected-(P26-Pad1)") (class "Default")
      (node (ref "P26") (pin "1") (pinfunction "1_1") (pintype "passive+no_connect"))
    )
    (net (code "189") (name "unconnected-(P26-Pad2)") (class "Default")
      (node (ref "P26") (pin "2") (pinfunction "2_2") (pintype "passive+no_connect"))
    )
    (net (code "190") (name "unconnected-(P26-Pad3)") (class "Default")
      (node (ref "P26") (pin "3") (pinfunction "3_3") (pintype "passive+no_connect"))
    )
    (net (code "191") (name "unconnected-(P26-Pad4)") (class "Default")
      (node (ref "P26") (pin "4") (pinfunction "4_4") (pintype "passive+no_connect"))
    )
    (net (code "192") (name "unconnected-(P26-Pad5)") (class "Default")
      (node (ref "P26") (pin "5") (pinfunction "5_5") (pintype "passive+no_connect"))
    )
    (net (code "193") (name "unconnected-(P27-Pad1)") (class "Default")
      (node (ref "P27") (pin "1") (pinfunction "1_1") (pintype "passive+no_connect"))
    )
    (net (code "194") (name "unconnected-(P27-Pad2)") (class "Default")
      (node (ref "P27") (pin "2") (pinfunction "2_2") (pintype "passive+no_connect"))
    )
    (net (code "195") (name "unconnected-(P27-Pad3)") (class "Default")
      (node (ref "P27") (pin "3") (pinfunction "3_3") (pintype "passive+no_connect"))
    )
    (net (code "196") (name "unconnected-(P27-Pad4)") (class "Default")
      (node (ref "P27") (pin "4") (pinfunction "4_4") (pintype "passive+no_connect"))
    )
    (net (code "197") (name "unconnected-(P27-Pad5)") (class "Default")
      (node (ref "P27") (pin "5") (pinfunction "5_5") (pintype "passive+no_connect"))
    )
    (net (code "198") (name "unconnected-(U5-NC-Pad7)") (class "Default")
      (node (ref "U5") (pin "7") (pinfunction "NC_7") (pintype "passive+no_connect"))
    )
    (net (code "199") (name "unconnected-(U5-NC-Pad8)") (class "Default")
      (node (ref "U5") (pin "8") (pinfunction "NC_8") (pintype "passive+no_connect"))
    )
    (net (code "200") (name "unconnected-(U5-NC-Pad9)") (class "Default")
      (node (ref "U5") (pin "9") (pinfunction "NC_9") (pintype "passive+no_connect"))
    )
    (net (code "201") (name "unconnected-(U5-NC-Pad10)") (class "Default")
      (node (ref "U5") (pin "10") (pinfunction "NC_10") (pintype "passive+no_connect"))
    )
    (net (code "202") (name "unconnected-(U5-~{FAULT}-Pad6)") (class "Default")
      (node (ref "U5") (pin "6") (pinfunction "~{FAULT}_6") (pintype "open_collector+no_connect"))
    )
    (net (code "203") (name "unconnected-(U6-NC-Pad7)") (class "Default")
      (node (ref "U6") (pin "7") (pinfunction "NC_7") (pintype "passive+no_connect"))
    )
    (net (code "204") (name "unconnected-(U6-NC-Pad8)") (class "Default")
      (node (ref "U6") (pin "8") (pinfunction "NC_8") (pintype "passive+no_connect"))
    )
    (net (code "205") (name "unconnected-(U6-NC-Pad9)") (class "Default")
      (node (ref "U6") (pin "9") (pinfunction "NC_9") (pintype "passive+no_connect"))
    )
    (net (code "206") (name "unconnected-(U6-NC-Pad10)") (class "Default")
      (node (ref "U6") (pin "10") (pinfunction "NC_10") (pintype "passive+no_connect"))
    )
    (net (code "207") (name "unconnected-(U6-~{FAULT}-Pad6)") (class "Default")
      (node (ref "U6") (pin "6") (pinfunction "~{FAULT}_6") (pintype "open_collector+no_connect"))
    )
    (net (code "208") (name "unconnected-(U7-NC-Pad7)") (class "Default")
      (node (ref "U7") (pin "7") (pinfunction "NC_7") (pintype "passive+no_connect"))
    )
    (net (code "209") (name "unconnected-(U7-NC-Pad8)") (class "Default")
      (node (ref "U7") (pin "8") (pinfunction "NC_8") (pintype "passive+no_connect"))
    )
    (net (code "210") (name "unconnected-(U7-NC-Pad9)") (class "Default")
      (node (ref "U7") (pin "9") (pinfunction "NC_9") (pintype "passive+no_connect"))
    )
    (net (code "211") (name "unconnected-(U7-NC-Pad10)") (class "Default")
      (node (ref "U7") (pin "10") (pinfunction "NC_10") (pintype "passive+no_connect"))
    )
    (net (code "212") (name "unconnected-(U7-~{FAULT}-Pad6)") (class "Default")
      (node (ref "U7") (pin "6") (pinfunction "~{FAULT}_6") (pintype "open_collector+no_connect"))
    )
  )
)
